# LED_OSRAM.net
KiCad netlist of a schematic drawn in Altium Designer
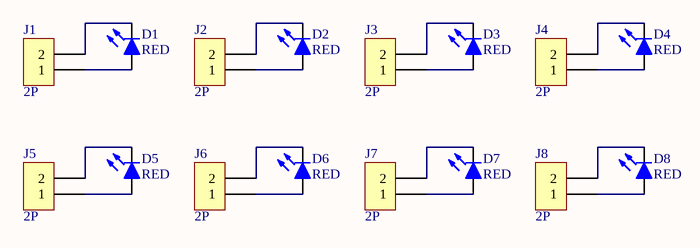
[diagram p0: LED OSRAM.SchDoc]

(export (version "E")
  (design (tool "Eeschema 10.0.6"))
  (components
    (comp (ref "D1")
      (value "RED")
      (footprint "OSRAM_GOLDENDRAGON")
      (description "Typical INFRARED GaAs LED")
      (fields (field (name "Comment") "LED dán 0805RED") (field (name "PUBLISHER") "*"))
      (libsource (lib "DnsSchLib") (part "LED0"))
    )
    (comp (ref "D2")
      (value "RED")
      (footprint "OSRAM_GOLDENDRAGON")
      (description "Typical INFRARED GaAs LED")
      (fields (field (name "Comment") "LED dán 0805RED") (field (name "PUBLISHER") "*"))
      (libsource (lib "DnsSchLib") (part "LED0"))
    )
    (comp (ref "D3")
      (value "RED")
      (footprint "OSRAM_GOLDENDRAGON")
      (description "Typical INFRARED GaAs LED")
      (fields (field (name "Comment") "LED dán 0805RED") (field (name "PUBLISHER") "*"))
      (libsource (lib "DnsSchLib") (part "LED0"))
    )
    (comp (ref "D4")
      (value "RED")
      (footprint "OSRAM_GOLDENDRAGON")
      (description "Typical INFRARED GaAs LED")
      (fields (field (name "Comment") "LED dán 0805RED") (field (name "PUBLISHER") "*"))
      (libsource (lib "DnsSchLib") (part "LED0"))
    )
    (comp (ref "D5")
      (value "RED")
      (footprint "OSRAM_GOLDENDRAGON")
      (description "Typical INFRARED GaAs LED")
      (fields (field (name "Comment") "LED dán 0805RED") (field (name "PUBLISHER") "*"))
      (libsource (lib "DnsSchLib") (part "LED0"))
    )
    (comp (ref "D6")
      (value "RED")
      (footprint "OSRAM_GOLDENDRAGON")
      (description "Typical INFRARED GaAs LED")
      (fields (field (name "Comment") "LED dán 0805RED") (field (name "PUBLISHER") "*"))
      (libsource (lib "DnsSchLib") (part "LED0"))
    )
    (comp (ref "D7")
      (value "RED")
      (footprint "OSRAM_GOLDENDRAGON")
      (description "Typical INFRARED GaAs LED")
      (fields (field (name "Comment") "LED dán 0805RED") (field (name "PUBLISHER") "*"))
      (libsource (lib "DnsSchLib") (part "LED0"))
    )
    (comp (ref "D8")
      (value "RED")
      (footprint "OSRAM_GOLDENDRAGON")
      (description "Typical INFRARED GaAs LED")
      (fields (field (name "Comment") "LED dán 0805RED") (field (name "PUBLISHER") "*"))
      (libsource (lib "DnsSchLib") (part "LED0"))
    )
    (comp (ref "J1")
      (value "2P")
      (footprint "HDR1x2")
      (fields (field (name "Comment") "Jump đực loại cong, 2.54mm2P"))
      (libsource (lib "DnsSchLib") (part "CON2"))
    )
    (comp (ref "J2")
      (value "2P")
      (footprint "HDR1x2")
      (fields (field (name "Comment") "Jump đực loại cong, 2.54mm2P"))
      (libsource (lib "DnsSchLib") (part "CON2"))
    )
    (comp (ref "J3")
      (value "2P")
      (footprint "HDR1x2")
      (fields (field (name "Comment") "Jump đực loại cong, 2.54mm2P"))
      (libsource (lib "DnsSchLib") (part "CON2"))
    )
    (comp (ref "J4")
      (value "2P")
      (footprint "HDR1x2")
      (fields (field (name "Comment") "Jump đực loại cong, 2.54mm2P"))
      (libsource (lib "DnsSchLib") (part "CON2"))
    )
    (comp (ref "J5")
      (value "2P")
      (footprint "HDR1x2")
      (fields (field (name "Comment") "Jump đực loại cong, 2.54mm2P"))
      (libsource (lib "DnsSchLib") (part "CON2"))
    )
    (comp (ref "J6")
      (value "2P")
      (footprint "HDR1x2")
      (fields (field (name "Comment") "Jump đực loại cong, 2.54mm2P"))
      (libsource (lib "DnsSchLib") (part "CON2"))
    )
    (comp (ref "J7")
      (value "2P")
      (footprint "HDR1x2")
      (fields (field (name "Comment") "Jump đực loại cong, 2.54mm2P"))
      (libsource (lib "DnsSchLib") (part "CON2"))
    )
    (comp (ref "J8")
      (value "2P")
      (footprint "HDR1x2")
      (fields (field (name "Comment") "Jump đực loại cong, 2.54mm2P"))
      (libsource (lib "DnsSchLib") (part "CON2"))
    )
  )
  (nets
    (net (code "1") (name "Net-(D1-A)") (class "Default")
      (node (ref "D1") (pin "1") (pinfunction "A_1") (pintype "passive"))
      (node (ref "J1") (pin "1") (pinfunction "1_1") (pintype "passive"))
    )
    (net (code "2") (name "Net-(D1-K)") (class "Default")
      (node (ref "D1") (pin "2") (pinfunction "K_2") (pintype "passive"))
      (node (ref "J1") (pin "2") (pinfunction "2_2") (pintype "passive"))
    )
    (net (code "3") (name "Net-(D2-A)") (class "Default")
      (node (ref "D2") (pin "1") (pinfunction "A_1") (pintype "passive"))
      (node (ref "J2") (pin "1") (pinfunction "1_1") (pintype "passive"))
    )
    (net (code "4") (name "Net-(D2-K)") (class "Default")
      (node (ref "D2") (pin "2") (pinfunction "K_2") (pintype "passive"))
      (node (ref "J2") (pin "2") (pinfunction "2_2") (pintype "passive"))
    )
    (net (code "5") (name "Net-(D3-A)") (class "Default")
      (node (ref "D3") (pin "1") (pinfunction "A_1") (pintype "passive"))
      (node (ref "J3") (pin "1") (pinfunction "1_1") (pintype "passive"))
    )
    (net (code "6") (name "Net-(D3-K)") (class "Default")
      (node (ref "D3") (pin "2") (pinfunction "K_2") (pintype "passive"))
      (node (ref "J3") (pin "2") (pinfunction "2_2") (pintype "passive"))
    )
    (net (code "7") (name "Net-(D4-A)") (class "Default")
      (node (ref "D4") (pin "1") (pinfunction "A_1") (pintype "passive"))
      (node (ref "J4") (pin "1") (pinfunction "1_1") (pintype "passive"))
    )
    (net (code "8") (name "Net-(D4-K)") (class "Default")
      (node (ref "D4") (pin "2") (pinfunction "K_2") (pintype "passive"))
      (node (ref "J4") (pin "2") (pinfunction "2_2") (pintype "passive"))
    )
    (net (code "9") (name "Net-(D5-A)") (class "Default")
      (node (ref "D5") (pin "1") (pinfunction "A_1") (pintype "passive"))
      (node (ref "J5") (pin "1") (pinfunction "1_1") (pintype "passive"))
    )
    (net (code "10") (name "Net-(D5-K)") (class "Default")
      (node (ref "D5") (pin "2") (pinfunction "K_2") (pintype "passive"))
      (node (ref "J5") (pin "2") (pinfunction "2_2") (pintype "passive"))
    )
    (net (code "11") (name "Net-(D6-A)") (class "Default")
      (node (ref "D6") (pin "1") (pinfunction "A_1") (pintype "passive"))
      (node (ref "J6") (pin "1") (pinfunction "1_1") (pintype "passive"))
    )
    (net (code "12") (name "Net-(D6-K)") (class "Default")
      (node (ref "D6") (pin "2") (pinfunction "K_2") (pintype "passive"))
      (node (ref "J6") (pin "2") (pinfunction "2_2") (pintype "passive"))
    )
    (net (code "13") (name "Net-(D7-A)") (class "Default")
      (node (ref "D7") (pin "1") (pinfunction "A_1") (pintype "passive"))
      (node (ref "J7") (pin "1") (pinfunction "1_1") (pintype "passive"))
    )
    (net (code "14") (name "Net-(D7-K)") (class "Default")
      (node (ref "D7") (pin "2") (pinfunction "K_2") (pintype "passive"))
      (node (ref "J7") (pin "2") (pinfunction "2_2") (pintype "passive"))
    )
    (net (code "15") (name "Net-(D8-A)") (class "Default")
      (node (ref "D8") (pin "1") (pinfunction "A_1") (pintype "passive"))
      (node (ref "J8") (pin "1") (pinfunction "1_1") (pintype "passive"))
    )
    (net (code "16") (name "Net-(D8-K)") (class "Default")
      (node (ref "D8") (pin "2") (pinfunction "K_2") (pintype "passive"))
      (node (ref "J8") (pin "2") (pinfunction "2_2") (pintype "passive"))
    )
  )
)
